# MiniSystem-Sch.net
KiCad netlist of a schematic drawn in Altium Designer
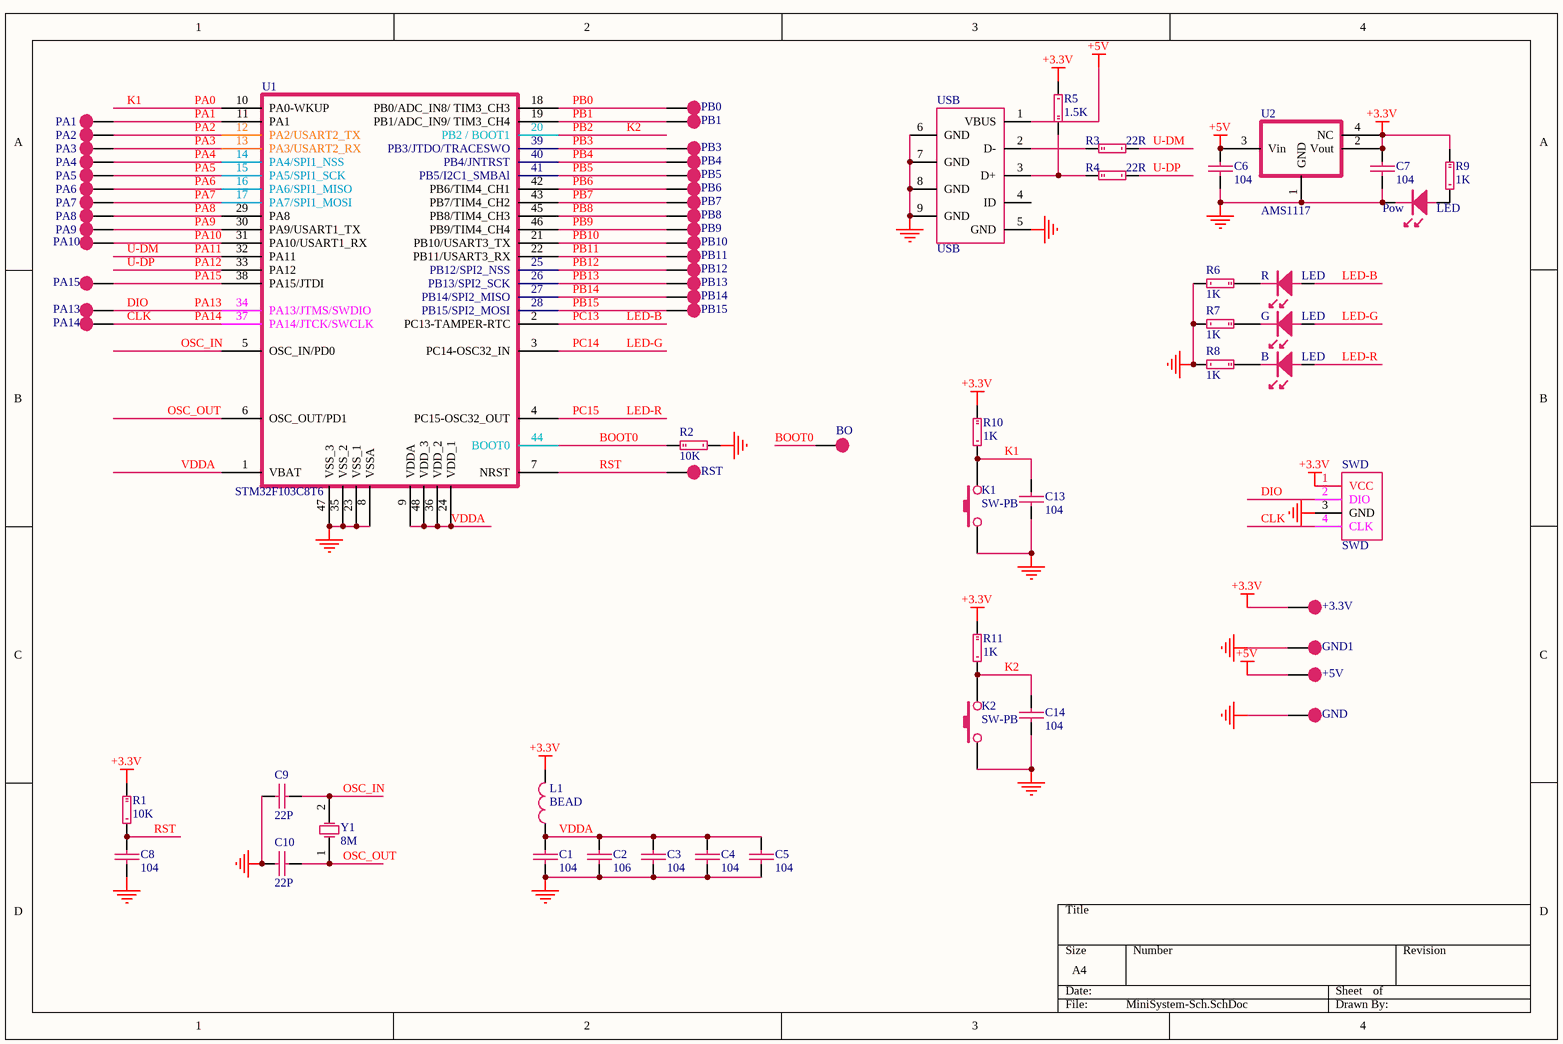
[diagram p0: MiniSystem-Sch.SchDoc]

(export (version "E")
  (design (tool "Eeschema 10.0.6"))
  (components
    (comp (ref "+3.3V")
      (value "~")
      (footprint "TP")
      (description "测试点/触摸点")
      (libsource (lib "Sch_Lib") (part "TP"))
    )
    (comp (ref "+5V")
      (value "~")
      (footprint "TP")
      (description "测试点/触摸点")
      (libsource (lib "Sch_Lib") (part "TP"))
    )
    (comp (ref "B")
      (value "LED")
      (footprint "LED0805")
      (description "LED灯")
      (libsource (lib "Sch_Lib") (part "LED"))
    )
    (comp (ref "BO")
      (value "~")
      (footprint "TP")
      (description "测试点/触摸点")
      (libsource (lib "Sch_Lib") (part "TP"))
    )
    (comp (ref "C1")
      (value "104")
      (footprint "C0603")
      (description "无极性电容")
      (libsource (lib "Sch_Lib") (part "CAP"))
    )
    (comp (ref "C2")
      (value "106")
      (footprint "C0805")
      (description "无极性电容")
      (libsource (lib "Sch_Lib") (part "CAP"))
    )
    (comp (ref "C3")
      (value "104")
      (footprint "C0603")
      (description "无极性电容")
      (libsource (lib "Sch_Lib") (part "CAP"))
    )
    (comp (ref "C4")
      (value "104")
      (footprint "C0603")
      (description "无极性电容")
      (libsource (lib "Sch_Lib") (part "CAP"))
    )
    (comp (ref "C5")
      (value "104")
      (footprint "C0603")
      (description "无极性电容")
      (libsource (lib "Sch_Lib") (part "CAP"))
    )
    (comp (ref "C6")
      (value "104")
      (footprint "C0603")
      (description "无极性电容")
      (libsource (lib "Sch_Lib") (part "CAP"))
    )
    (comp (ref "C7")
      (value "104")
      (footprint "C0603")
      (description "无极性电容")
      (libsource (lib "Sch_Lib") (part "CAP"))
    )
    (comp (ref "C8")
      (value "104")
      (footprint "C0603")
      (description "无极性电容")
      (libsource (lib "Sch_Lib") (part "CAP"))
    )
    (comp (ref "C9")
      (value "22P")
      (footprint "C0603")
      (description "无极性电容")
      (libsource (lib "Sch_Lib") (part "CAP"))
    )
    (comp (ref "C10")
      (value "22P")
      (footprint "C0603")
      (description "无极性电容")
      (libsource (lib "Sch_Lib") (part "CAP"))
    )
    (comp (ref "C13")
      (value "104")
      (footprint "C0603")
      (description "无极性电容")
      (libsource (lib "Sch_Lib") (part "CAP"))
    )
    (comp (ref "C14")
      (value "104")
      (footprint "C0603")
      (description "无极性电容")
      (libsource (lib "Sch_Lib") (part "CAP"))
    )
    (comp (ref "G")
      (value "LED")
      (footprint "LED0805")
      (description "LED灯")
      (libsource (lib "Sch_Lib") (part "LED"))
    )
    (comp (ref "GND")
      (value "~")
      (footprint "TP")
      (description "测试点/触摸点")
      (libsource (lib "Sch_Lib") (part "TP"))
    )
    (comp (ref "GND1")
      (value "~")
      (footprint "TP")
      (description "测试点/触摸点")
      (libsource (lib "Sch_Lib") (part "TP"))
    )
    (comp (ref "K1")
      (value "SW-PB")
      (footprint "SW-Mini")
      (description "按键")
      (libsource (lib "Sch_Lib") (part "SW-PB"))
    )
    (comp (ref "K2")
      (value "SW-PB")
      (footprint "SW-Mini")
      (description "按键")
      (libsource (lib "Sch_Lib") (part "SW-PB"))
    )
    (comp (ref "L1")
      (value "BEAD")
      (footprint "l0603")
      (description "磁珠")
      (libsource (lib "Sch_Lib") (part "INDUCTOR"))
    )
    (comp (ref "PA1")
      (value "~")
      (footprint "TP")
      (description "测试点/触摸点")
      (libsource (lib "Sch_Lib") (part "TP"))
    )
    (comp (ref "PA2")
      (value "~")
      (footprint "TP")
      (description "测试点/触摸点")
      (libsource (lib "Sch_Lib") (part "TP"))
    )
    (comp (ref "PA3")
      (value "~")
      (footprint "TP")
      (description "测试点/触摸点")
      (libsource (lib "Sch_Lib") (part "TP"))
    )
    (comp (ref "PA4")
      (value "~")
      (footprint "TP")
      (description "测试点/触摸点")
      (libsource (lib "Sch_Lib") (part "TP"))
    )
    (comp (ref "PA5")
      (value "~")
      (footprint "TP")
      (description "测试点/触摸点")
      (libsource (lib "Sch_Lib") (part "TP"))
    )
    (comp (ref "PA6")
      (value "~")
      (footprint "TP")
      (description "测试点/触摸点")
      (libsource (lib "Sch_Lib") (part "TP"))
    )
    (comp (ref "PA7")
      (value "~")
      (footprint "TP")
      (description "测试点/触摸点")
      (libsource (lib "Sch_Lib") (part "TP"))
    )
    (comp (ref "PA8")
      (value "~")
      (footprint "TP")
      (description "测试点/触摸点")
      (libsource (lib "Sch_Lib") (part "TP"))
    )
    (comp (ref "PA9")
      (value "~")
      (footprint "TP")
      (description "测试点/触摸点")
      (libsource (lib "Sch_Lib") (part "TP"))
    )
    (comp (ref "PA10")
      (value "~")
      (footprint "TP")
      (description "测试点/触摸点")
      (libsource (lib "Sch_Lib") (part "TP"))
    )
    (comp (ref "PA13")
      (value "~")
      (footprint "TP")
      (description "测试点/触摸点")
      (libsource (lib "Sch_Lib") (part "TP"))
    )
    (comp (ref "PA14")
      (value "~")
      (footprint "TP")
      (description "测试点/触摸点")
      (libsource (lib "Sch_Lib") (part "TP"))
    )
    (comp (ref "PA15")
      (value "~")
      (footprint "TP")
      (description "测试点/触摸点")
      (libsource (lib "Sch_Lib") (part "TP"))
    )
    (comp (ref "PB0")
      (value "~")
      (footprint "TP")
      (description "测试点/触摸点")
      (libsource (lib "Sch_Lib") (part "TP"))
    )
    (comp (ref "PB1")
      (value "~")
      (footprint "TP")
      (description "测试点/触摸点")
      (libsource (lib "Sch_Lib") (part "TP"))
    )
    (comp (ref "PB3")
      (value "~")
      (footprint "TP")
      (description "测试点/触摸点")
      (libsource (lib "Sch_Lib") (part "TP"))
    )
    (comp (ref "PB4")
      (value "~")
      (footprint "TP")
      (description "测试点/触摸点")
      (libsource (lib "Sch_Lib") (part "TP"))
    )
    (comp (ref "PB5")
      (value "~")
      (footprint "TP")
      (description "测试点/触摸点")
      (libsource (lib "Sch_Lib") (part "TP"))
    )
    (comp (ref "PB6")
      (value "~")
      (footprint "TP")
      (description "测试点/触摸点")
      (libsource (lib "Sch_Lib") (part "TP"))
    )
    (comp (ref "PB7")
      (value "~")
      (footprint "TP")
      (description "测试点/触摸点")
      (libsource (lib "Sch_Lib") (part "TP"))
    )
    (comp (ref "PB8")
      (value "~")
      (footprint "TP")
      (description "测试点/触摸点")
      (libsource (lib "Sch_Lib") (part "TP"))
    )
    (comp (ref "PB9")
      (value "~")
      (footprint "TP")
      (description "测试点/触摸点")
      (libsource (lib "Sch_Lib") (part "TP"))
    )
    (comp (ref "PB10")
      (value "~")
      (footprint "TP")
      (description "测试点/触摸点")
      (libsource (lib "Sch_Lib") (part "TP"))
    )
    (comp (ref "PB11")
      (value "~")
      (footprint "TP")
      (description "测试点/触摸点")
      (libsource (lib "Sch_Lib") (part "TP"))
    )
    (comp (ref "PB12")
      (value "~")
      (footprint "TP")
      (description "测试点/触摸点")
      (libsource (lib "Sch_Lib") (part "TP"))
    )
    (comp (ref "PB13")
      (value "~")
      (footprint "TP")
      (description "测试点/触摸点")
      (libsource (lib "Sch_Lib") (part "TP"))
    )
    (comp (ref "PB14")
      (value "~")
      (footprint "TP")
      (description "测试点/触摸点")
      (libsource (lib "Sch_Lib") (part "TP"))
    )
    (comp (ref "PB15")
      (value "~")
      (footprint "TP")
      (description "测试点/触摸点")
      (libsource (lib "Sch_Lib") (part "TP"))
    )
    (comp (ref "Pow")
      (value "LED")
      (footprint "LED0805")
      (description "LED灯")
      (libsource (lib "Sch_Lib") (part "LED"))
    )
    (comp (ref "R")
      (value "LED")
      (footprint "LED0805")
      (description "LED灯")
      (libsource (lib "Sch_Lib") (part "LED"))
    )
    (comp (ref "R1")
      (value "10K")
      (footprint "R0603")
      (description "贴片电阻")
      (libsource (lib "Sch_Lib") (part "RES2"))
    )
    (comp (ref "R2")
      (value "10K")
      (footprint "R0603")
      (description "贴片电阻")
      (libsource (lib "Sch_Lib") (part "RES2"))
    )
    (comp (ref "R3")
      (value "22R")
      (footprint "R0603")
      (description "贴片电阻")
      (libsource (lib "Sch_Lib") (part "RES2"))
    )
    (comp (ref "R4")
      (value "22R")
      (footprint "R0603")
      (description "贴片电阻")
      (libsource (lib "Sch_Lib") (part "RES2"))
    )
    (comp (ref "R5")
      (value "1.5K")
      (footprint "R0603")
      (description "贴片电阻")
      (libsource (lib "Sch_Lib") (part "RES2"))
    )
    (comp (ref "R6")
      (value "1K")
      (footprint "R0603")
      (description "贴片电阻")
      (libsource (lib "Sch_Lib") (part "RES2"))
    )
    (comp (ref "R7")
      (value "1K")
      (footprint "R0603")
      (description "贴片电阻")
      (libsource (lib "Sch_Lib") (part "RES2"))
    )
    (comp (ref "R8")
      (value "1K")
      (footprint "R0603")
      (description "贴片电阻")
      (libsource (lib "Sch_Lib") (part "RES2"))
    )
    (comp (ref "R9")
      (value "1K")
      (footprint "R0603")
      (description "贴片电阻")
      (libsource (lib "Sch_Lib") (part "RES2"))
    )
    (comp (ref "R10")
      (value "1K")
      (footprint "R0603")
      (description "贴片电阻")
      (libsource (lib "Sch_Lib") (part "RES2"))
    )
    (comp (ref "R11")
      (value "1K")
      (footprint "R0603")
      (description "贴片电阻")
      (libsource (lib "Sch_Lib") (part "RES2"))
    )
    (comp (ref "RST")
      (value "~")
      (footprint "TP")
      (description "测试点/触摸点")
      (libsource (lib "Sch_Lib") (part "TP"))
    )
    (comp (ref "SWD")
      (value "SWD")
      (footprint "SWIM_SWD")
      (description "SWD下载口(STM32)")
      (libsource (lib "Sch_Lib") (part "SWD"))
    )
    (comp (ref "U1")
      (value "STM32F103C8T6")
      (footprint "LQFP48")
      (description "STM32F1单片机48引脚")
      (libsource (lib "Sch_Lib") (part "STM32F103C8T6"))
    )
    (comp (ref "U2")
      (value "AMS1117")
      (footprint "SOT223")
      (description "稳压芯片(LDO)")
      (libsource (lib "Sch_Lib") (part "AMS1117"))
    )
    (comp (ref "USB")
      (value "USB")
      (footprint "USB-Micro")
      (description "通用串行总线(USB)")
      (libsource (lib "Sch_Lib") (part "USB"))
    )
    (comp (ref "Y1")
      (value "8M")
      (footprint "XTAL-(5.0X3.2MM)-2P")
      (description "晶振")
      (libsource (lib "Sch_Lib") (part "XTAL"))
    )
  )
  (nets
    (net (code "1") (name "+3.3V") (class "Default")
      (node (ref "+3.3V") (pin "1") (pinfunction "1_1") (pintype "passive"))
      (node (ref "C7") (pin "1") (pinfunction "1_1") (pintype "passive"))
      (node (ref "L1") (pin "2") (pinfunction "2_2") (pintype "passive"))
      (node (ref "R1") (pin "2") (pinfunction "2_2") (pintype "passive"))
      (node (ref "R10") (pin "2") (pinfunction "2_2") (pintype "passive"))
      (node (ref "R11") (pin "2") (pinfunction "2_2") (pintype "passive"))
      (node (ref "R5") (pin "1") (pinfunction "1_1") (pintype "passive"))
      (node (ref "R9") (pin "2") (pinfunction "2_2") (pintype "passive"))
      (node (ref "SWD") (pin "1") (pinfunction "VCC_1") (pintype "passive"))
      (node (ref "U2") (pin "2") (pinfunction "Vout_2") (pintype "passive"))
      (node (ref "U2") (pin "4") (pinfunction "NC_4") (pintype "passive"))
    )
    (net (code "2") (name "+5V") (class "Default")
      (node (ref "+5V") (pin "1") (pinfunction "1_1") (pintype "passive"))
      (node (ref "C6") (pin "1") (pinfunction "1_1") (pintype "passive"))
      (node (ref "U2") (pin "3") (pinfunction "Vin_3") (pintype "passive"))
      (node (ref "USB") (pin "1") (pinfunction "VBUS_1") (pintype "passive"))
    )
    (net (code "3") (name "/BOOT0") (class "Default")
      (node (ref "BO") (pin "1") (pinfunction "1_1") (pintype "passive"))
      (node (ref "R2") (pin "2") (pinfunction "2_2") (pintype "passive"))
      (node (ref "U1") (pin "44") (pinfunction "BOOT0_44") (pintype "passive"))
    )
    (net (code "4") (name "/CLK") (class "Default")
      (node (ref "PA14") (pin "1") (pinfunction "1_1") (pintype "passive"))
      (node (ref "SWD") (pin "4") (pinfunction "CLK_4") (pintype "passive"))
      (node (ref "U1") (pin "37") (pinfunction "PA14/JTCK/SWCLK_37") (pintype "passive"))
    )
    (net (code "5") (name "/DIO") (class "Default")
      (node (ref "PA13") (pin "1") (pinfunction "1_1") (pintype "passive"))
      (node (ref "SWD") (pin "2") (pinfunction "DIO_2") (pintype "passive"))
      (node (ref "U1") (pin "34") (pinfunction "PA13/JTMS/SWDIO_34") (pintype "passive"))
    )
    (net (code "6") (name "/K1") (class "Default")
      (node (ref "C13") (pin "2") (pinfunction "2_2") (pintype "passive"))
      (node (ref "K1") (pin "2") (pinfunction "2_2") (pintype "passive"))
      (node (ref "R10") (pin "1") (pinfunction "1_1") (pintype "passive"))
      (node (ref "U1") (pin "10") (pinfunction "PA0-WKUP_10") (pintype "passive"))
    )
    (net (code "7") (name "/K2") (class "Default")
      (node (ref "C14") (pin "2") (pinfunction "2_2") (pintype "passive"))
      (node (ref "K2") (pin "2") (pinfunction "2_2") (pintype "passive"))
      (node (ref "R11") (pin "1") (pinfunction "1_1") (pintype "passive"))
      (node (ref "U1") (pin "20") (pinfunction "PB2_/_BOOT1_20") (pintype "passive"))
    )
    (net (code "8") (name "/LED-B") (class "Default")
      (node (ref "R") (pin "1") (pinfunction "1_1") (pintype "passive"))
      (node (ref "U1") (pin "2") (pinfunction "PC13-TAMPER-RTC_2") (pintype "passive"))
    )
    (net (code "9") (name "/LED-G") (class "Default")
      (node (ref "G") (pin "1") (pinfunction "1_1") (pintype "passive"))
      (node (ref "U1") (pin "3") (pinfunction "PC14-OSC32_IN_3") (pintype "passive"))
    )
    (net (code "10") (name "/LED-R") (class "Default")
      (node (ref "B") (pin "1") (pinfunction "1_1") (pintype "passive"))
      (node (ref "U1") (pin "4") (pinfunction "PC15-OSC32_OUT_4") (pintype "passive"))
    )
    (net (code "11") (name "/OSC_IN") (class "Default")
      (node (ref "C9") (pin "2") (pinfunction "2_2") (pintype "passive"))
      (node (ref "U1") (pin "5") (pinfunction "OSC_IN/PD0_5") (pintype "passive"))
      (node (ref "Y1") (pin "2") (pinfunction "OSC2_2") (pintype "passive"))
    )
    (net (code "12") (name "/OSC_OUT") (class "Default")
      (node (ref "C10") (pin "2") (pinfunction "2_2") (pintype "passive"))
      (node (ref "U1") (pin "6") (pinfunction "OSC_OUT/PD1_6") (pintype "passive"))
      (node (ref "Y1") (pin "1") (pinfunction "OSC1_1") (pintype "passive"))
    )
    (net (code "13") (name "/PA1") (class "Default")
      (node (ref "PA1") (pin "1") (pinfunction "1_1") (pintype "passive"))
      (node (ref "U1") (pin "11") (pinfunction "PA1_11") (pintype "passive"))
    )
    (net (code "14") (name "/PA2") (class "Default")
      (node (ref "PA2") (pin "1") (pinfunction "1_1") (pintype "passive"))
      (node (ref "U1") (pin "12") (pinfunction "PA2/USART2_TX_12") (pintype "passive"))
    )
    (net (code "15") (name "/PA3") (class "Default")
      (node (ref "PA3") (pin "1") (pinfunction "1_1") (pintype "passive"))
      (node (ref "U1") (pin "13") (pinfunction "PA3/USART2_RX_13") (pintype "passive"))
    )
    (net (code "16") (name "/PA4") (class "Default")
      (node (ref "PA4") (pin "1") (pinfunction "1_1") (pintype "passive"))
      (node (ref "U1") (pin "14") (pinfunction "PA4/SPI1_NSS_14") (pintype "passive"))
    )
    (net (code "17") (name "/PA5") (class "Default")
      (node (ref "PA5") (pin "1") (pinfunction "1_1") (pintype "passive"))
      (node (ref "U1") (pin "15") (pinfunction "PA5/SPI1_SCK_15") (pintype "passive"))
    )
    (net (code "18") (name "/PA6") (class "Default")
      (node (ref "PA6") (pin "1") (pinfunction "1_1") (pintype "passive"))
      (node (ref "U1") (pin "16") (pinfunction "PA6/SPI1_MISO_16") (pintype "passive"))
    )
    (net (code "19") (name "/PA7") (class "Default")
      (node (ref "PA7") (pin "1") (pinfunction "1_1") (pintype "passive"))
      (node (ref "U1") (pin "17") (pinfunction "PA7/SPI1_MOSI_17") (pintype "passive"))
    )
    (net (code "20") (name "/PA8") (class "Default")
      (node (ref "PA8") (pin "1") (pinfunction "1_1") (pintype "passive"))
      (node (ref "U1") (pin "29") (pinfunction "PA8_29") (pintype "passive"))
    )
    (net (code "21") (name "/PA9") (class "Default")
      (node (ref "PA9") (pin "1") (pinfunction "1_1") (pintype "passive"))
      (node (ref "U1") (pin "30") (pinfunction "PA9/USART1_TX_30") (pintype "passive"))
    )
    (net (code "22") (name "/PA10") (class "Default")
      (node (ref "PA10") (pin "1") (pinfunction "1_1") (pintype "passive"))
      (node (ref "U1") (pin "31") (pinfunction "PA10/USART1_RX_31") (pintype "passive"))
    )
    (net (code "23") (name "/PA11") (class "Default")
      (node (ref "R3") (pin "1") (pinfunction "1_1") (pintype "passive"))
      (node (ref "U1") (pin "32") (pinfunction "PA11_32") (pintype "passive"))
    )
    (net (code "24") (name "/PA12") (class "Default")
      (node (ref "R4") (pin "1") (pinfunction "1_1") (pintype "passive"))
      (node (ref "U1") (pin "33") (pinfunction "PA12_33") (pintype "passive"))
    )
    (net (code "25") (name "/PA15") (class "Default")
      (node (ref "PA15") (pin "1") (pinfunction "1_1") (pintype "passive"))
      (node (ref "U1") (pin "38") (pinfunction "PA15/JTDI_38") (pintype "passive"))
    )
    (net (code "26") (name "/PB0") (class "Default")
      (node (ref "PB0") (pin "1") (pinfunction "1_1") (pintype "passive"))
      (node (ref "U1") (pin "18") (pinfunction "PB0/ADC_IN8/_TIM3_CH3_18") (pintype "passive"))
    )
    (net (code "27") (name "/PB1") (class "Default")
      (node (ref "PB1") (pin "1") (pinfunction "1_1") (pintype "passive"))
      (node (ref "U1") (pin "19") (pinfunction "PB1/ADC_IN9/_TIM3_CH4_19") (pintype "passive"))
    )
    (net (code "28") (name "/PB3") (class "Default")
      (node (ref "PB3") (pin "1") (pinfunction "1_1") (pintype "passive"))
      (node (ref "U1") (pin "39") (pinfunction "PB3/JTDO/TRACESWO_39") (pintype "passive"))
    )
    (net (code "29") (name "/PB4") (class "Default")
      (node (ref "PB4") (pin "1") (pinfunction "1_1") (pintype "passive"))
      (node (ref "U1") (pin "40") (pinfunction "PB4/JNTRST_40") (pintype "passive"))
    )
    (net (code "30") (name "/PB5") (class "Default")
      (node (ref "PB5") (pin "1") (pinfunction "1_1") (pintype "passive"))
      (node (ref "U1") (pin "41") (pinfunction "PB5/I2C1_SMBAl_41") (pintype "passive"))
    )
    (net (code "31") (name "/PB6") (class "Default")
      (node (ref "PB6") (pin "1") (pinfunction "1_1") (pintype "passive"))
      (node (ref "U1") (pin "42") (pinfunction "PB6/TIM4_CH1_42") (pintype "passive"))
    )
    (net (code "32") (name "/PB7") (class "Default")
      (node (ref "PB7") (pin "1") (pinfunction "1_1") (pintype "passive"))
      (node (ref "U1") (pin "43") (pinfunction "PB7/TIM4_CH2_43") (pintype "passive"))
    )
    (net (code "33") (name "/PB8") (class "Default")
      (node (ref "PB8") (pin "1") (pinfunction "1_1") (pintype "passive"))
      (node (ref "U1") (pin "45") (pinfunction "PB8/TIM4_CH3_45") (pintype "passive"))
    )
    (net (code "34") (name "/PB9") (class "Default")
      (node (ref "PB9") (pin "1") (pinfunction "1_1") (pintype "passive"))
      (node (ref "U1") (pin "46") (pinfunction "PB9/TIM4_CH4_46") (pintype "passive"))
    )
    (net (code "35") (name "/PB10") (class "Default")
      (node (ref "PB10") (pin "1") (pinfunction "1_1") (pintype "passive"))
      (node (ref "U1") (pin "21") (pinfunction "PB10/USART3_TX_21") (pintype "passive"))
    )
    (net (code "36") (name "/PB11") (class "Default")
      (node (ref "PB11") (pin "1") (pinfunction "1_1") (pintype "passive"))
      (node (ref "U1") (pin "22") (pinfunction "PB11/USART3_RX_22") (pintype "passive"))
    )
    (net (code "37") (name "/PB12") (class "Default")
      (node (ref "PB12") (pin "1") (pinfunction "1_1") (pintype "passive"))
      (node (ref "U1") (pin "25") (pinfunction "PB12/SPI2_NSS_25") (pintype "passive"))
    )
    (net (code "38") (name "/PB13") (class "Default")
      (node (ref "PB13") (pin "1") (pinfunction "1_1") (pintype "passive"))
      (node (ref "U1") (pin "26") (pinfunction "PB13/SPI2_SCK_26") (pintype "passive"))
    )
    (net (code "39") (name "/PB14") (class "Default")
      (node (ref "PB14") (pin "1") (pinfunction "1_1") (pintype "passive"))
      (node (ref "U1") (pin "27") (pinfunction "PB14/SPI2_MISO_27") (pintype "passive"))
    )
    (net (code "40") (name "/PB15") (class "Default")
      (node (ref "PB15") (pin "1") (pinfunction "1_1") (pintype "passive"))
      (node (ref "U1") (pin "28") (pinfunction "PB15/SPI2_MOSI_28") (pintype "passive"))
    )
    (net (code "41") (name "/RST") (class "Default")
      (node (ref "C8") (pin "1") (pinfunction "1_1") (pintype "passive"))
      (node (ref "R1") (pin "1") (pinfunction "1_1") (pintype "passive"))
      (node (ref "RST") (pin "1") (pinfunction "1_1") (pintype "passive"))
      (node (ref "U1") (pin "7") (pinfunction "NRST_7") (pintype "passive"))
    )
    (net (code "42") (name "/VDDA") (class "Default")
      (node (ref "C1") (pin "1") (pinfunction "1_1") (pintype "passive"))
      (node (ref "C2") (pin "1") (pinfunction "1_1") (pintype "passive"))
      (node (ref "C3") (pin "1") (pinfunction "1_1") (pintype "passive"))
      (node (ref "C4") (pin "1") (pinfunction "1_1") (pintype "passive"))
      (node (ref "C5") (pin "1") (pinfunction "1_1") (pintype "passive"))
      (node (ref "L1") (pin "1") (pinfunction "1_1") (pintype "passive"))
      (node (ref "U1") (pin "1") (pinfunction "VBAT_1") (pintype "passive"))
      (node (ref "U1") (pin "24") (pinfunction "VDD_1_24") (pintype "passive"))
      (node (ref "U1") (pin "36") (pinfunction "VDD_2_36") (pintype "passive"))
      (node (ref "U1") (pin "48") (pinfunction "VDD_3_48") (pintype "passive"))
      (node (ref "U1") (pin "9") (pinfunction "VDDA_9") (pintype "passive"))
    )
    (net (code "43") (name "GND") (class "Default")
      (node (ref "C1") (pin "2") (pinfunction "2_2") (pintype "passive"))
      (node (ref "C10") (pin "1") (pinfunction "1_1") (pintype "passive"))
      (node (ref "C13") (pin "1") (pinfunction "1_1") (pintype "passive"))
      (node (ref "C14") (pin "1") (pinfunction "1_1") (pintype "passive"))
      (node (ref "C2") (pin "2") (pinfunction "2_2") (pintype "passive"))
      (node (ref "C3") (pin "2") (pinfunction "2_2") (pintype "passive"))
      (node (ref "C4") (pin "2") (pinfunction "2_2") (pintype "passive"))
      (node (ref "C5") (pin "2") (pinfunction "2_2") (pintype "passive"))
      (node (ref "C6") (pin "2") (pinfunction "2_2") (pintype "passive"))
      (node (ref "C7") (pin "2") (pinfunction "2_2") (pintype "passive"))
      (node (ref "C8") (pin "2") (pinfunction "2_2") (pintype "passive"))
      (node (ref "C9") (pin "1") (pinfunction "1_1") (pintype "passive"))
      (node (ref "GND") (pin "1") (pinfunction "1_1") (pintype "passive"))
      (node (ref "GND1") (pin "1") (pinfunction "1_1") (pintype "passive"))
      (node (ref "K1") (pin "1") (pinfunction "1_1") (pintype "passive"))
      (node (ref "K2") (pin "1") (pinfunction "1_1") (pintype "passive"))
      (node (ref "Pow") (pin "2") (pinfunction "2_2") (pintype "passive"))
      (node (ref "R2") (pin "1") (pinfunction "1_1") (pintype "passive"))
      (node (ref "R6") (pin "1") (pinfunction "1_1") (pintype "passive"))
      (node (ref "R7") (pin "1") (pinfunction "1_1") (pintype "passive"))
      (node (ref "R8") (pin "1") (pinfunction "1_1") (pintype "passive"))
      (node (ref "SWD") (pin "3") (pinfunction "GND_3") (pintype "passive"))
      (node (ref "U1") (pin "23") (pinfunction "VSS_1_23") (pintype "passive"))
      (node (ref "U1") (pin "35") (pinfunction "VSS_2_35") (pintype "passive"))
      (node (ref "U1") (pin "47") (pinfunction "VSS_3_47") (pintype "passive"))
      (node (ref "U1") (pin "8") (pinfunction "VSSA_8") (pintype "passive"))
      (node (ref "U2") (pin "1") (pinfunction "GND_1") (pintype "passive"))
      (node (ref "USB") (pin "5") (pinfunction "GND_5") (pintype "passive"))
      (node (ref "USB") (pin "6") (pinfunction "GND_6") (pintype "power_in"))
      (node (ref "USB") (pin "7") (pinfunction "GND_7") (pintype "power_in"))
      (node (ref "USB") (pin "8") (pinfunction "GND_8") (pintype "power_in"))
      (node (ref "USB") (pin "9") (pinfunction "GND_9") (pintype "power_in"))
    )
    (net (code "44") (name "Net-(B-Pad2)") (class "Default")
      (node (ref "B") (pin "2") (pinfunction "2_2") (pintype "passive"))
      (node (ref "R8") (pin "2") (pinfunction "2_2") (pintype "passive"))
    )
    (net (code "45") (name "Net-(G-Pad2)") (class "Default")
      (node (ref "G") (pin "2") (pinfunction "2_2") (pintype "passive"))
      (node (ref "R7") (pin "2") (pinfunction "2_2") (pintype "passive"))
    )
    (net (code "46") (name "Net-(Pow-Pad1)") (class "Default")
      (node (ref "Pow") (pin "1") (pinfunction "1_1") (pintype "passive"))
      (node (ref "R9") (pin "1") (pinfunction "1_1") (pintype "passive"))
    )
    (net (code "47") (name "Net-(R-Pad2)") (class "Default")
      (node (ref "R") (pin "2") (pinfunction "2_2") (pintype "passive"))
      (node (ref "R6") (pin "2") (pinfunction "2_2") (pintype "passive"))
    )
    (net (code "48") (name "Net-(USB-D+)") (class "Default")
      (node (ref "R4") (pin "2") (pinfunction "2_2") (pintype "passive"))
      (node (ref "R5") (pin "2") (pinfunction "2_2") (pintype "passive"))
      (node (ref "USB") (pin "3") (pinfunction "D+_3") (pintype "passive"))
    )
    (net (code "49") (name "Net-(USB-D-)") (class "Default")
      (node (ref "R3") (pin "2") (pinfunction "2_2") (pintype "passive"))
      (node (ref "USB") (pin "2") (pinfunction "D-_2") (pintype "passive"))
    )
    (net (code "50") (name "unconnected-(USB-ID-Pad4)") (class "Default")
      (node (ref "USB") (pin "4") (pinfunction "ID_4") (pintype "passive"))
    )
  )
)
